# darkgame-controller-revb.net
KiCad netlist of a schematic drawn in EAGLE
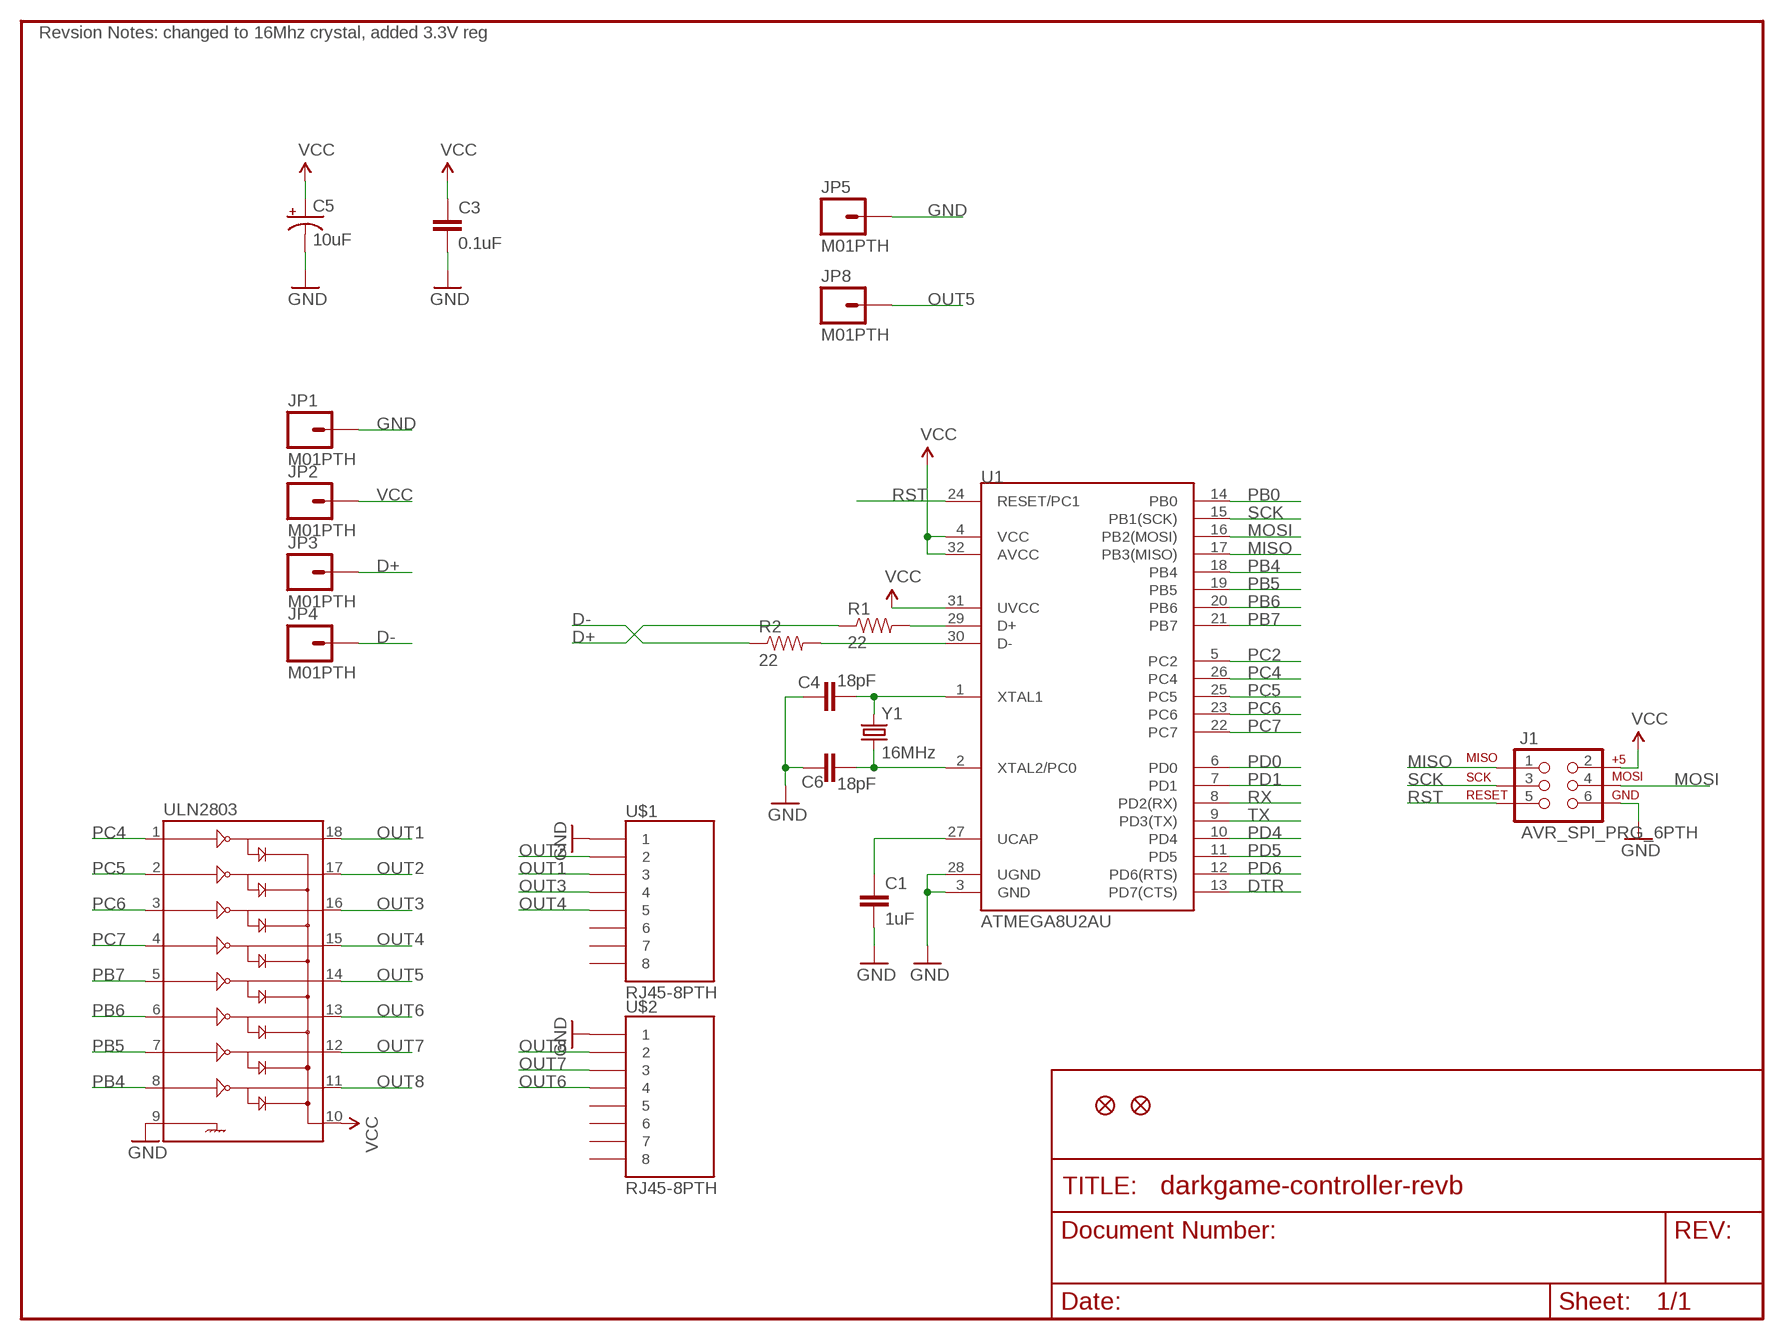
[diagram p0: schematic, sheet 1]

(export (version "E")
  (design (tool "Eeschema 10.0.6"))
  (components
    (comp (ref "C1")
      (value "1uF")
      (footprint "eagle-import:0805")
      (libsource (lib "eagle-import") (part "CAP0805"))
    )
    (comp (ref "C3")
      (value "0.1uF")
      (footprint "eagle-import:0805")
      (libsource (lib "eagle-import") (part "CAP0805"))
    )
    (comp (ref "C4")
      (value "18pF")
      (footprint "eagle-import:0805")
      (libsource (lib "eagle-import") (part "CAP0805"))
    )
    (comp (ref "C5")
      (value "10uF")
      (footprint "eagle-import:EIA3216")
      (libsource (lib "eagle-import") (part "CAP_POL1206"))
    )
    (comp (ref "C6")
      (value "18pF")
      (footprint "eagle-import:0805")
      (libsource (lib "eagle-import") (part "CAP0805"))
    )
    (comp (ref "J1")
      (value "AVR_SPI_PRG_6PTH")
      (footprint "eagle-import:2X3")
      (libsource (lib "eagle-import") (part "AVR_SPI_PRG_6PTH"))
    )
    (comp (ref "JP1")
      (value "M01PTH")
      (footprint "eagle-import:1X01")
      (libsource (lib "eagle-import") (part "M01PTH"))
    )
    (comp (ref "JP2")
      (value "M01PTH")
      (footprint "eagle-import:1X01")
      (libsource (lib "eagle-import") (part "M01PTH"))
    )
    (comp (ref "JP3")
      (value "M01PTH")
      (footprint "eagle-import:1X01")
      (libsource (lib "eagle-import") (part "M01PTH"))
    )
    (comp (ref "JP4")
      (value "M01PTH")
      (footprint "eagle-import:1X01")
      (libsource (lib "eagle-import") (part "M01PTH"))
    )
    (comp (ref "JP5")
      (value "M01PTH")
      (footprint "eagle-import:1X01")
      (libsource (lib "eagle-import") (part "M01PTH"))
    )
    (comp (ref "JP6")
      (value "FIDUCIAL1X2")
      (footprint "eagle-import:FIDUCIAL-1X2")
      (libsource (lib "eagle-import") (part "FIDUCIAL1X2"))
    )
    (comp (ref "JP7")
      (value "FIDUCIAL1X2")
      (footprint "eagle-import:FIDUCIAL-1X2")
      (libsource (lib "eagle-import") (part "FIDUCIAL1X2"))
    )
    (comp (ref "JP8")
      (value "M01PTH")
      (footprint "eagle-import:1X01")
      (libsource (lib "eagle-import") (part "M01PTH"))
    )
    (comp (ref "R1")
      (value "22")
      (footprint "eagle-import:0805")
      (libsource (lib "eagle-import") (part "RESISTOR0805-RES"))
    )
    (comp (ref "R2")
      (value "22")
      (footprint "eagle-import:0805")
      (libsource (lib "eagle-import") (part "RESISTOR0805-RES"))
    )
    (comp (ref "U$1")
      (value "RJ45-8PTH")
      (footprint "eagle-import:RJ45-8")
      (libsource (lib "eagle-import") (part "RJ45-8PTH"))
    )
    (comp (ref "U$2")
      (value "RJ45-8PTH")
      (footprint "eagle-import:RJ45-8")
      (libsource (lib "eagle-import") (part "RJ45-8PTH"))
    )
    (comp (ref "U1")
      (value "ATMEGA8U2AU")
      (footprint "eagle-import:TQFP32-08")
      (libsource (lib "eagle-import") (part "ATMEGA8U2AU"))
    )
    (comp (ref "ULN2803")
      (value "ULN2803SOICW")
      (footprint "eagle-import:SO18L")
      (libsource (lib "eagle-import") (part "ULN2803SOICW"))
    )
    (comp (ref "Y1")
      (value "16MHz")
      (footprint "eagle-import:CRYSTAL-SMD-5X3")
      (libsource (lib "eagle-import") (part "CRYSTAL5X3"))
    )
  )
  (nets
    (net (code "1") (name "/D+") (class "Default")
      (node (ref "JP3") (pin "1") (pinfunction "1_1") (pintype "passive"))
      (node (ref "R1") (pin "1") (pinfunction "1_1") (pintype "passive"))
    )
    (net (code "2") (name "/D-") (class "Default")
      (node (ref "JP4") (pin "1") (pinfunction "1_1") (pintype "passive"))
      (node (ref "R2") (pin "1") (pinfunction "1_1") (pintype "passive"))
    )
    (net (code "3") (name "/DTR") (class "Default")
      (node (ref "U1") (pin "13") (pinfunction "PD7(CTS)_13") (pintype "bidirectional"))
    )
    (net (code "4") (name "/MISO") (class "Default")
      (node (ref "J1") (pin "1") (pinfunction "1_1") (pintype "passive"))
      (node (ref "U1") (pin "17") (pinfunction "PB3(MISO)_17") (pintype "bidirectional"))
    )
    (net (code "5") (name "/MOSI") (class "Default")
      (node (ref "J1") (pin "4") (pinfunction "4_4") (pintype "passive"))
      (node (ref "U1") (pin "16") (pinfunction "PB2(MOSI)_16") (pintype "bidirectional"))
    )
    (net (code "6") (name "/OUT1") (class "Default")
      (node (ref "U$1") (pin "3") (pinfunction "3_3") (pintype "bidirectional"))
      (node (ref "ULN2803") (pin "18") (pinfunction "18_18") (pintype "bidirectional"))
    )
    (net (code "7") (name "/OUT2") (class "Default")
      (node (ref "U$1") (pin "2") (pinfunction "2_2") (pintype "bidirectional"))
      (node (ref "ULN2803") (pin "17") (pinfunction "17_17") (pintype "bidirectional"))
    )
    (net (code "8") (name "/OUT3") (class "Default")
      (node (ref "U$1") (pin "4") (pinfunction "4_4") (pintype "bidirectional"))
      (node (ref "ULN2803") (pin "16") (pinfunction "16_16") (pintype "bidirectional"))
    )
    (net (code "9") (name "/OUT4") (class "Default")
      (node (ref "U$1") (pin "5") (pinfunction "5_5") (pintype "bidirectional"))
      (node (ref "ULN2803") (pin "15") (pinfunction "15_15") (pintype "bidirectional"))
    )
    (net (code "10") (name "/OUT5") (class "Default")
      (node (ref "JP8") (pin "1") (pinfunction "1_1") (pintype "passive"))
      (node (ref "ULN2803") (pin "14") (pinfunction "14_14") (pintype "bidirectional"))
    )
    (net (code "11") (name "/OUT6") (class "Default")
      (node (ref "U$2") (pin "4") (pinfunction "4_4") (pintype "bidirectional"))
      (node (ref "ULN2803") (pin "13") (pinfunction "13_13") (pintype "bidirectional"))
    )
    (net (code "12") (name "/OUT7") (class "Default")
      (node (ref "U$2") (pin "3") (pinfunction "3_3") (pintype "bidirectional"))
      (node (ref "ULN2803") (pin "12") (pinfunction "12_12") (pintype "bidirectional"))
    )
    (net (code "13") (name "/OUT8") (class "Default")
      (node (ref "U$2") (pin "2") (pinfunction "2_2") (pintype "bidirectional"))
      (node (ref "ULN2803") (pin "11") (pinfunction "11_11") (pintype "bidirectional"))
    )
    (net (code "14") (name "/PB0") (class "Default")
      (node (ref "U1") (pin "14") (pinfunction "PB0_14") (pintype "bidirectional"))
    )
    (net (code "15") (name "/PB4") (class "Default")
      (node (ref "U1") (pin "18") (pinfunction "PB4_18") (pintype "bidirectional"))
      (node (ref "ULN2803") (pin "8") (pinfunction "8_8") (pintype "bidirectional"))
    )
    (net (code "16") (name "/PB5") (class "Default")
      (node (ref "U1") (pin "19") (pinfunction "PB5_19") (pintype "bidirectional"))
      (node (ref "ULN2803") (pin "7") (pinfunction "7_7") (pintype "bidirectional"))
    )
    (net (code "17") (name "/PB6") (class "Default")
      (node (ref "U1") (pin "20") (pinfunction "PB6_20") (pintype "bidirectional"))
      (node (ref "ULN2803") (pin "6") (pinfunction "6_6") (pintype "bidirectional"))
    )
    (net (code "18") (name "/PB7") (class "Default")
      (node (ref "U1") (pin "21") (pinfunction "PB7_21") (pintype "bidirectional"))
      (node (ref "ULN2803") (pin "5") (pinfunction "5_5") (pintype "bidirectional"))
    )
    (net (code "19") (name "/PC2") (class "Default")
      (node (ref "U1") (pin "5") (pinfunction "PC2_5") (pintype "bidirectional"))
    )
    (net (code "20") (name "/PC4") (class "Default")
      (node (ref "U1") (pin "26") (pinfunction "PC4_26") (pintype "bidirectional"))
      (node (ref "ULN2803") (pin "1") (pinfunction "1_1") (pintype "bidirectional"))
    )
    (net (code "21") (name "/PC5") (class "Default")
      (node (ref "U1") (pin "25") (pinfunction "PC5_25") (pintype "bidirectional"))
      (node (ref "ULN2803") (pin "2") (pinfunction "2_2") (pintype "bidirectional"))
    )
    (net (code "22") (name "/PC6") (class "Default")
      (node (ref "U1") (pin "23") (pinfunction "PC6_23") (pintype "bidirectional"))
      (node (ref "ULN2803") (pin "3") (pinfunction "3_3") (pintype "bidirectional"))
    )
    (net (code "23") (name "/PC7") (class "Default")
      (node (ref "U1") (pin "22") (pinfunction "PC7_22") (pintype "bidirectional"))
      (node (ref "ULN2803") (pin "4") (pinfunction "4_4") (pintype "bidirectional"))
    )
    (net (code "24") (name "/PD0") (class "Default")
      (node (ref "U1") (pin "6") (pinfunction "PD0_6") (pintype "bidirectional"))
    )
    (net (code "25") (name "/PD1") (class "Default")
      (node (ref "U1") (pin "7") (pinfunction "PD1_7") (pintype "bidirectional"))
    )
    (net (code "26") (name "/PD4") (class "Default")
      (node (ref "U1") (pin "10") (pinfunction "PD4_10") (pintype "bidirectional"))
    )
    (net (code "27") (name "/PD5") (class "Default")
      (node (ref "U1") (pin "11") (pinfunction "PD5_11") (pintype "bidirectional"))
    )
    (net (code "28") (name "/PD6") (class "Default")
      (node (ref "U1") (pin "12") (pinfunction "PD6(RTS)_12") (pintype "bidirectional"))
    )
    (net (code "29") (name "/RST") (class "Default")
      (node (ref "J1") (pin "5") (pinfunction "5_5") (pintype "passive"))
      (node (ref "U1") (pin "24") (pinfunction "RESET/PC1_24") (pintype "bidirectional"))
    )
    (net (code "30") (name "/RX") (class "Default")
      (node (ref "U1") (pin "8") (pinfunction "PD2(RX)_8") (pintype "bidirectional"))
    )
    (net (code "31") (name "/SCK") (class "Default")
      (node (ref "J1") (pin "3") (pinfunction "3_3") (pintype "passive"))
      (node (ref "U1") (pin "15") (pinfunction "PB1(SCK)_15") (pintype "bidirectional"))
    )
    (net (code "32") (name "/TX") (class "Default")
      (node (ref "U1") (pin "9") (pinfunction "PD3(TX)_9") (pintype "bidirectional"))
    )
    (net (code "33") (name "GND") (class "Default")
      (node (ref "C1") (pin "2") (pinfunction "2_2") (pintype "passive"))
      (node (ref "C3") (pin "2") (pinfunction "2_2") (pintype "passive"))
      (node (ref "C4") (pin "2") (pinfunction "2_2") (pintype "passive"))
      (node (ref "C5") (pin "C") (pinfunction "-_C") (pintype "passive"))
      (node (ref "C6") (pin "2") (pinfunction "2_2") (pintype "passive"))
      (node (ref "J1") (pin "6") (pinfunction "6_6") (pintype "passive"))
      (node (ref "JP1") (pin "1") (pinfunction "1_1") (pintype "passive"))
      (node (ref "JP5") (pin "1") (pinfunction "1_1") (pintype "passive"))
      (node (ref "U$1") (pin "1") (pinfunction "1_1") (pintype "bidirectional"))
      (node (ref "U$2") (pin "1") (pinfunction "1_1") (pintype "bidirectional"))
      (node (ref "U1") (pin "28") (pinfunction "UGND_28") (pintype "bidirectional"))
      (node (ref "U1") (pin "3") (pinfunction "GND_3") (pintype "bidirectional"))
      (node (ref "ULN2803") (pin "9") (pinfunction "9_9") (pintype "bidirectional"))
    )
    (net (code "34") (name "Net-(U1-D+)") (class "Default")
      (node (ref "R1") (pin "2") (pinfunction "2_2") (pintype "passive"))
      (node (ref "U1") (pin "29") (pinfunction "D+_29") (pintype "bidirectional"))
    )
    (net (code "35") (name "Net-(U1-D-)") (class "Default")
      (node (ref "R2") (pin "2") (pinfunction "2_2") (pintype "passive"))
      (node (ref "U1") (pin "30") (pinfunction "D-_30") (pintype "bidirectional"))
    )
    (net (code "36") (name "Net-(U1-UCAP)") (class "Default")
      (node (ref "C1") (pin "1") (pinfunction "1_1") (pintype "passive"))
      (node (ref "U1") (pin "27") (pinfunction "UCAP_27") (pintype "bidirectional"))
    )
    (net (code "37") (name "Net-(U1-XTAL1)") (class "Default")
      (node (ref "C4") (pin "1") (pinfunction "1_1") (pintype "passive"))
      (node (ref "U1") (pin "1") (pinfunction "XTAL1_1") (pintype "bidirectional"))
      (node (ref "Y1") (pin "3") (pinfunction "2_3") (pintype "passive"))
    )
    (net (code "38") (name "Net-(U1-XTAL2{slash}PC0)") (class "Default")
      (node (ref "C6") (pin "1") (pinfunction "1_1") (pintype "passive"))
      (node (ref "U1") (pin "2") (pinfunction "XTAL2/PC0_2") (pintype "bidirectional"))
      (node (ref "Y1") (pin "1") (pinfunction "1_1") (pintype "passive"))
    )
    (net (code "39") (name "VCC") (class "Default")
      (node (ref "C3") (pin "1") (pinfunction "1_1") (pintype "passive"))
      (node (ref "C5") (pin "A") (pinfunction "+_A") (pintype "passive"))
      (node (ref "J1") (pin "2") (pinfunction "2_2") (pintype "passive"))
      (node (ref "JP2") (pin "1") (pinfunction "1_1") (pintype "passive"))
      (node (ref "U1") (pin "31") (pinfunction "UVCC_31") (pintype "bidirectional"))
      (node (ref "U1") (pin "32") (pinfunction "AVCC_32") (pintype "bidirectional"))
      (node (ref "U1") (pin "4") (pinfunction "VCC_4") (pintype "bidirectional"))
      (node (ref "ULN2803") (pin "10") (pinfunction "10_10") (pintype "bidirectional"))
    )
    (net (code "40") (name "unconnected-(U$1-Pad6)") (class "Default")
      (node (ref "U$1") (pin "6") (pinfunction "6_6") (pintype "bidirectional"))
    )
    (net (code "41") (name "unconnected-(U$1-Pad7)") (class "Default")
      (node (ref "U$1") (pin "7") (pinfunction "7_7") (pintype "bidirectional"))
    )
    (net (code "42") (name "unconnected-(U$1-Pad8)") (class "Default")
      (node (ref "U$1") (pin "8") (pinfunction "8_8") (pintype "bidirectional"))
    )
    (net (code "43") (name "unconnected-(U$2-Pad5)") (class "Default")
      (node (ref "U$2") (pin "5") (pinfunction "5_5") (pintype "bidirectional"))
    )
    (net (code "44") (name "unconnected-(U$2-Pad6)") (class "Default")
      (node (ref "U$2") (pin "6") (pinfunction "6_6") (pintype "bidirectional"))
    )
    (net (code "45") (name "unconnected-(U$2-Pad7)") (class "Default")
      (node (ref "U$2") (pin "7") (pinfunction "7_7") (pintype "bidirectional"))
    )
    (net (code "46") (name "unconnected-(U$2-Pad8)") (class "Default")
      (node (ref "U$2") (pin "8") (pinfunction "8_8") (pintype "bidirectional"))
    )
  )
)
